# ControllerV3_0_1.net
KiCad netlist of a schematic drawn in Altium Designer
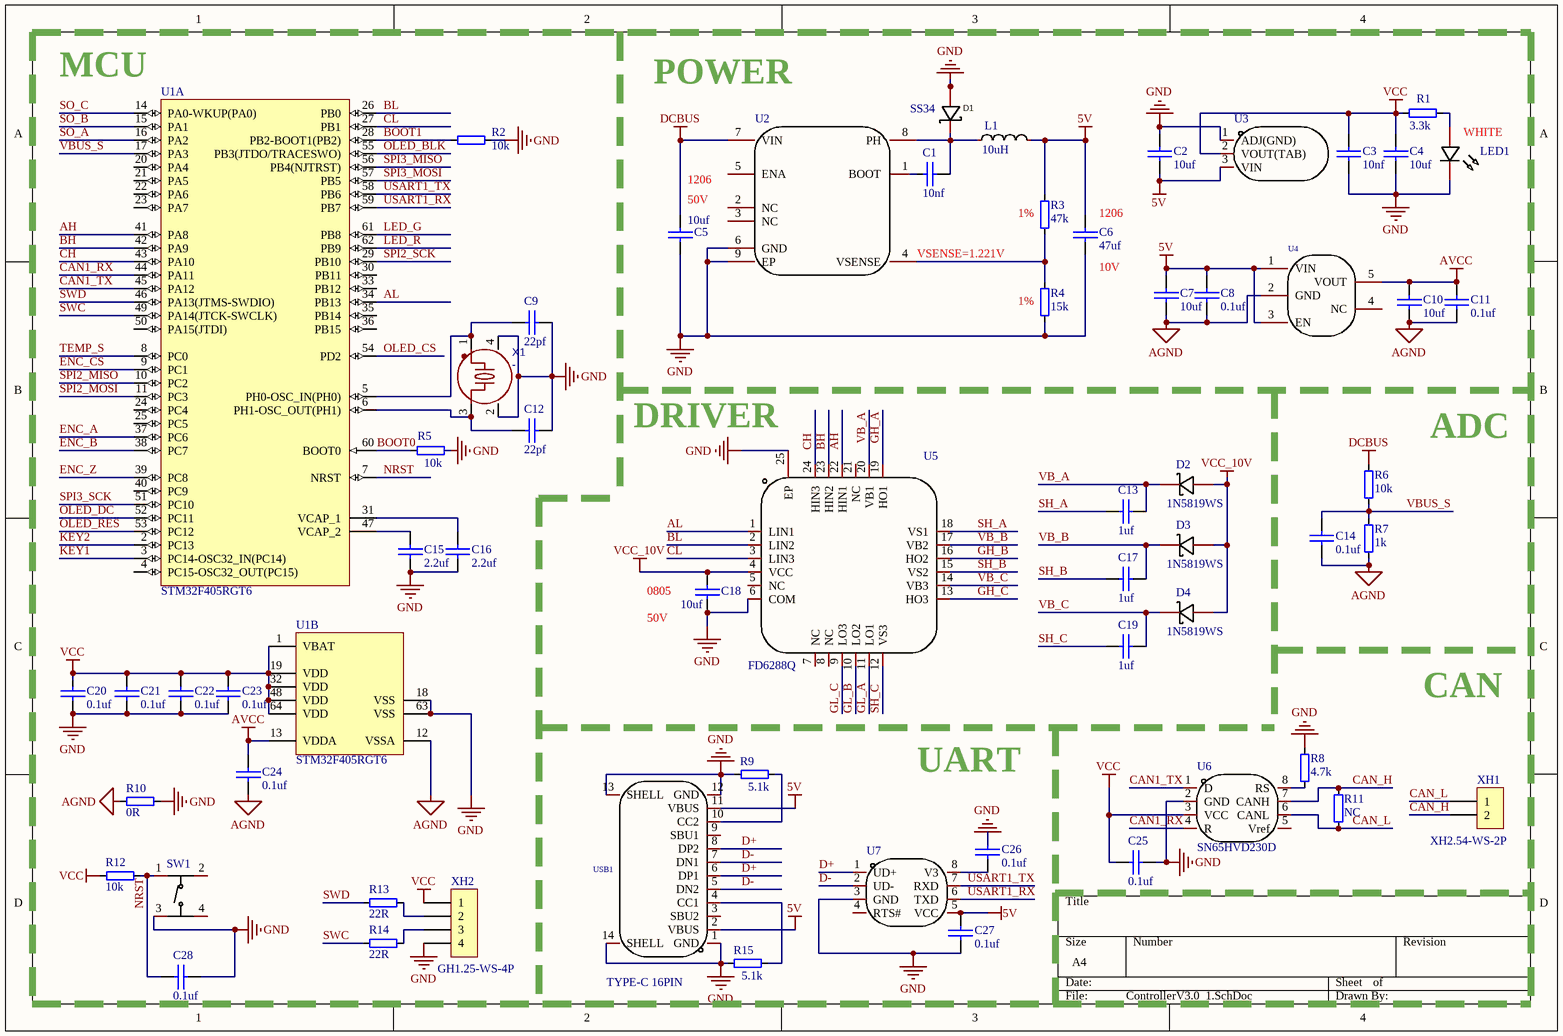
[diagram p0: ControllerV3.0_1.SchDoc]

(export (version "E")
  (design (tool "Eeschema 10.0.6"))
  (components
    (comp (ref "C1")
      (value "10nf")
      (footprint "0603C")
      (description "贴片电容")
      (libsource (lib "Controller") (part "CAP"))
    )
    (comp (ref "C2")
      (value "10uf")
      (footprint "0603C")
      (description "贴片电容")
      (libsource (lib "Controller") (part "CAP"))
    )
    (comp (ref "C3")
      (value "10nf")
      (footprint "0603C")
      (description "贴片电容")
      (libsource (lib "Controller") (part "CAP"))
    )
    (comp (ref "C4")
      (value "10uf")
      (footprint "0603C")
      (description "贴片电容")
      (libsource (lib "Controller") (part "CAP"))
    )
    (comp (ref "C5")
      (value "10uf")
      (footprint "1206C")
      (description "贴片电容")
      (libsource (lib "Controller") (part "CAP"))
    )
    (comp (ref "C6")
      (value "47uf")
      (footprint "1206C")
      (description "贴片电容")
      (libsource (lib "Controller") (part "CAP"))
    )
    (comp (ref "C7")
      (value "10uf")
      (footprint "0603C")
      (description "贴片电容")
      (libsource (lib "Controller") (part "CAP"))
    )
    (comp (ref "C8")
      (value "0.1uf")
      (footprint "0603C")
      (description "贴片电容")
      (libsource (lib "Controller") (part "CAP"))
    )
    (comp (ref "C9")
      (value "22pf")
      (footprint "0603C")
      (description "贴片电容")
      (libsource (lib "Controller") (part "CAP"))
    )
    (comp (ref "C10")
      (value "10uf")
      (footprint "0603C")
      (description "贴片电容")
      (libsource (lib "Controller") (part "CAP"))
    )
    (comp (ref "C11")
      (value "0.1uf")
      (footprint "0603C")
      (description "贴片电容")
      (libsource (lib "Controller") (part "CAP"))
    )
    (comp (ref "C12")
      (value "22pf")
      (footprint "0603C")
      (description "贴片电容")
      (libsource (lib "Controller") (part "CAP"))
    )
    (comp (ref "C13")
      (value "1uf")
      (footprint "0603C")
      (description "贴片电容")
      (libsource (lib "Controller") (part "CAP"))
    )
    (comp (ref "C14")
      (value "0.1uf")
      (footprint "0603C")
      (description "贴片电容")
      (libsource (lib "Controller") (part "CAP"))
    )
    (comp (ref "C15")
      (value "2.2uf")
      (footprint "0603C")
      (description "贴片电容")
      (libsource (lib "Controller") (part "CAP"))
    )
    (comp (ref "C16")
      (value "2.2uf")
      (footprint "0603C")
      (description "贴片电容")
      (libsource (lib "Controller") (part "CAP"))
    )
    (comp (ref "C17")
      (value "1uf")
      (footprint "0603C")
      (description "贴片电容")
      (libsource (lib "Controller") (part "CAP"))
    )
    (comp (ref "C18")
      (value "10uf")
      (footprint "0805C")
      (description "贴片电容")
      (libsource (lib "Controller") (part "CAP"))
    )
    (comp (ref "C19")
      (value "1uf")
      (footprint "0603C")
      (description "贴片电容")
      (libsource (lib "Controller") (part "CAP"))
    )
    (comp (ref "C20")
      (value "0.1uf")
      (footprint "0603C")
      (description "贴片电容")
      (libsource (lib "Controller") (part "CAP"))
    )
    (comp (ref "C21")
      (value "0.1uf")
      (footprint "0603C")
      (description "贴片电容")
      (libsource (lib "Controller") (part "CAP"))
    )
    (comp (ref "C22")
      (value "0.1uf")
      (footprint "0603C")
      (description "贴片电容")
      (libsource (lib "Controller") (part "CAP"))
    )
    (comp (ref "C23")
      (value "0.1uf")
      (footprint "0603C")
      (description "贴片电容")
      (libsource (lib "Controller") (part "CAP"))
    )
    (comp (ref "C24")
      (value "0.1uf")
      (footprint "0603C")
      (description "贴片电容")
      (libsource (lib "Controller") (part "CAP"))
    )
    (comp (ref "C25")
      (value "0.1uf")
      (footprint "0603C")
      (description "贴片电容")
      (libsource (lib "Controller") (part "CAP"))
    )
    (comp (ref "C26")
      (value "0.1uf")
      (footprint "0603C")
      (description "贴片电容")
      (libsource (lib "Controller") (part "CAP"))
    )
    (comp (ref "C27")
      (value "0.1uf")
      (footprint "0603C")
      (description "贴片电容")
      (libsource (lib "Controller") (part "CAP"))
    )
    (comp (ref "C28")
      (value "0.1uf")
      (footprint "0603C")
      (description "贴片电容")
      (libsource (lib "Controller") (part "CAP"))
    )
    (comp (ref "D1")
      (value "SS34")
      (footprint "SS34")
      (description "肖特基二极管")
      (fields (field (name "MANUFACTURER") "MDD"))
      (libsource (lib "Controller") (part "SS34"))
    )
    (comp (ref "D2")
      (value "1N5819WS")
      (footprint "SOD-323")
      (description "肖特基二极管")
      (fields (field (name "MANUFACTURER") "Hottech(合科泰)"))
      (libsource (lib "Controller") (part "1N5819WS"))
    )
    (comp (ref "D3")
      (value "1N5819WS")
      (footprint "SOD-323")
      (description "肖特基二极管")
      (fields (field (name "MANUFACTURER") "Hottech(合科泰)"))
      (libsource (lib "Controller") (part "1N5819WS"))
    )
    (comp (ref "D4")
      (value "1N5819WS")
      (footprint "SOD-323")
      (description "肖特基二极管")
      (fields (field (name "MANUFACTURER") "Hottech(合科泰)"))
      (libsource (lib "Controller") (part "1N5819WS"))
    )
    (comp (ref "L1")
      (value "10uH")
      (footprint "SMD-0420")
      (description "功率电感")
      (libsource (lib "Controller") (part "IND"))
    )
    (comp (ref "LED1")
      (value "LED_0603-B")
      (footprint "LED_0603")
      (libsource (lib "Controller") (part "LED"))
    )
    (comp (ref "R1")
      (value "3.3k")
      (footprint "0603R")
      (description "贴片电阻")
      (libsource (lib "Controller") (part "RES"))
    )
    (comp (ref "R2")
      (value "10k")
      (footprint "0603R")
      (description "贴片电阻")
      (libsource (lib "Controller") (part "RES"))
    )
    (comp (ref "R3")
      (value "47k")
      (footprint "0603R")
      (description "贴片电阻")
      (libsource (lib "Controller") (part "RES"))
    )
    (comp (ref "R4")
      (value "15k")
      (footprint "0603R")
      (description "贴片电阻")
      (libsource (lib "Controller") (part "RES"))
    )
    (comp (ref "R5")
      (value "10k")
      (footprint "0603R")
      (description "贴片电阻")
      (libsource (lib "Controller") (part "RES"))
    )
    (comp (ref "R6")
      (value "10k")
      (footprint "0603R")
      (description "贴片电阻")
      (libsource (lib "Controller") (part "RES"))
    )
    (comp (ref "R7")
      (value "1k")
      (footprint "0603R")
      (description "贴片电阻")
      (libsource (lib "Controller") (part "RES"))
    )
    (comp (ref "R8")
      (value "4.7k")
      (footprint "0603R")
      (description "贴片电阻")
      (libsource (lib "Controller") (part "RES"))
    )
    (comp (ref "R9")
      (value "5.1k")
      (footprint "0603R")
      (description "贴片电阻")
      (libsource (lib "Controller") (part "RES"))
    )
    (comp (ref "R10")
      (value "0R")
      (footprint "0603R")
      (description "贴片电阻")
      (libsource (lib "Controller") (part "RES"))
    )
    (comp (ref "R11")
      (value "NC")
      (footprint "0603R")
      (description "贴片电阻")
      (libsource (lib "Controller") (part "RES"))
    )
    (comp (ref "R12")
      (value "10k")
      (footprint "0603R")
      (description "贴片电阻")
      (libsource (lib "Controller") (part "RES"))
    )
    (comp (ref "R13")
      (value "22R")
      (footprint "0603R")
      (description "贴片电阻")
      (libsource (lib "Controller") (part "RES"))
    )
    (comp (ref "R14")
      (value "22R")
      (footprint "0603R")
      (description "贴片电阻")
      (libsource (lib "Controller") (part "RES"))
    )
    (comp (ref "R15")
      (value "5.1k")
      (footprint "0603R")
      (description "贴片电阻")
      (libsource (lib "Controller") (part "RES"))
    )
    (comp (ref "SW1")
      (value "TS-1187A-B-A-B")
      (footprint "TSW SMD-4*4*1.5")
      (description "轻触开关")
      (fields (field (name "MANUFACTURER") "XKB Connectivity(中国星坤)"))
      (libsource (lib "Controller") (part "TS-1187A-B-A-B"))
    )
    (comp (ref "U1")
      (value "STM32F405RGT6")
      (footprint "LQFP_64")
      (fields (field (name "MANUFACTURER") "STMicroelectronics"))
      (libsource (lib "Controller") (part "STM32F405RGT6"))
    )
    (comp (ref "U2")
      (value "TPS5450DDAR")
      (footprint "SOP-8-EP")
      (fields (field (name "MANUFACTURER") "TI(德州仪器)"))
      (libsource (lib "Controller") (part "TPS5450DDAR"))
    )
    (comp (ref "U3")
      (value "AMS1117-3.3_C347256")
      (footprint "SOT-89")
      (description "输出类型:固定;输出极性:正;最大输入电压:18V;输出电压:3.3V;输出电流:1A;电源纹波抑制比(PSRR):60dB@(120Hz);")
      (fields (field (name "MANUFACTURER") "UMW(友台半导体)") (field (name "MANUFACTURER PART") "AMS1117-3.3"))
      (libsource (lib "Controller") (part "AMS1117-3.3_C347256"))
    )
    (comp (ref "U4")
      (value "RT9013-33GB")
      (footprint "SOT-23-5")
      (description "输出类型:固定;输出极性:正;最大输入电压:5.5V;输出电压:3.3V;输出电流:500mA;电源纹波抑制比(PSRR):50dB@(10kHz);")
      (fields (field (name "MANUFACTURER") "RICHTEK(立锜)"))
      (libsource (lib "Controller") (part "RT9013-33GB"))
    )
    (comp (ref "U5")
      (value "FD6288Q")
      (footprint "QFN-24-EP(4x4)")
      (fields (field (name "MANUFACTURER") "Fortior Tech(峰岹)"))
      (libsource (lib "Controller") (part "FD6288Q"))
    )
    (comp (ref "U6")
      (value "SN65HVD230D")
      (footprint "SOP-8")
      (description "具有待机模式的 3.3V CAN 收发器 8-SOIC -40 to 85")
      (fields (field (name "MANUFACTURER") "TI(德州仪器)"))
      (libsource (lib "Controller") (part "SN65HVD230D"))
    )
    (comp (ref "U7")
      (value "CH340N")
      (footprint "SOP-8")
      (fields (field (name "MANUFACTURER") "WCH(南京沁恒)"))
      (libsource (lib "Controller") (part "CH340N"))
    )
    (comp (ref "USB1")
      (value "TYPE-C 16PIN")
      (footprint "USB-C-SMD_TYPE-C-6PIN-2MD-073")
      (description "连接器类型:Type-C;标准:-;公母:母座;触点数量:16;端口数量:1;安装方式:卧贴;额定电流 - 电源:5A;工作温度范围:-25℃~+85℃;")
      (fields
        (field (name "MANUFACTURER") "SHOU HAN(首韩)")
        (field (name "MANUFACTURER PART") "TYPE-C 16PIN 2MD(073)")
      )
      (libsource (lib "Controller") (part "TYPE-C 16PIN 2MD(073)"))
    )
    (comp (ref "X1")
      (value "-")
      (footprint "OSC 3225-4P")
      (description "8MHz")
      (fields
        (field (name "BOM_SUPPLIER PART") "C843260")
        (field (name "BOM_MANUFACTURER PART") "NX2016SA-32MHZ-STD-CZS-5")
        (field (name "CONTRIBUTOR") "LCSC")
      )
      (libsource (lib "Controller") (part "四脚无源晶振"))
    )
    (comp (ref "XH1")
      (value "XH2.54-WS-2P")
      (footprint "XH2.54-WS-2P")
      (libsource (lib "Controller") (part "XH2.54-WS-2P"))
    )
    (comp (ref "XH2")
      (value "GH1.25-WS-4P")
      (footprint "GH1.25-WS-4P")
      (libsource (lib "Controller") (part "GH1.25-WS-4P"))
    )
  )
  (nets
    (net (code "1") (name "/AH") (class "Default")
      (node (ref "U1") (pin "41") (pinfunction "PA8_41") (pintype "bidirectional"))
      (node (ref "U5") (pin "22") (pinfunction "HIN1_22") (pintype "passive"))
    )
    (net (code "2") (name "/AL") (class "Default")
      (node (ref "U1") (pin "34") (pinfunction "PB13_34") (pintype "bidirectional"))
      (node (ref "U5") (pin "1") (pinfunction "LIN1_1") (pintype "passive"))
    )
    (net (code "3") (name "/BH") (class "Default")
      (node (ref "U1") (pin "42") (pinfunction "PA9_42") (pintype "bidirectional"))
      (node (ref "U5") (pin "23") (pinfunction "HIN2_23") (pintype "passive"))
    )
    (net (code "4") (name "/BL") (class "Default")
      (node (ref "U1") (pin "26") (pinfunction "PB0_26") (pintype "bidirectional"))
      (node (ref "U5") (pin "2") (pinfunction "LIN2_2") (pintype "passive"))
    )
    (net (code "5") (name "/BOOT0") (class "Default")
      (node (ref "R5") (pin "1") (pinfunction "1_1") (pintype "passive"))
      (node (ref "U1") (pin "60") (pinfunction "BOOT0_60") (pintype "input"))
    )
    (net (code "6") (name "/BOOT1") (class "Default")
      (node (ref "R2") (pin "1") (pinfunction "1_1") (pintype "passive"))
      (node (ref "U1") (pin "28") (pinfunction "PB2-BOOT1(PB2)_28") (pintype "bidirectional"))
    )
    (net (code "7") (name "/CAN1_RX") (class "Default")
      (node (ref "U1") (pin "44") (pinfunction "PA11_44") (pintype "bidirectional"))
      (node (ref "U6") (pin "4") (pinfunction "R_4") (pintype "passive"))
    )
    (net (code "8") (name "/CAN1_TX") (class "Default")
      (node (ref "U1") (pin "45") (pinfunction "PA12_45") (pintype "bidirectional"))
      (node (ref "U6") (pin "1") (pinfunction "D_1") (pintype "passive"))
    )
    (net (code "9") (name "/CAN_H") (class "Default")
      (node (ref "R11") (pin "2") (pinfunction "2_2") (pintype "passive"))
      (node (ref "U6") (pin "7") (pinfunction "CANH_7") (pintype "passive"))
      (node (ref "XH1") (pin "2") (pinfunction "2_2") (pintype "passive"))
    )
    (net (code "10") (name "/CAN_L") (class "Default")
      (node (ref "R11") (pin "1") (pinfunction "1_1") (pintype "passive"))
      (node (ref "U6") (pin "6") (pinfunction "CANL_6") (pintype "passive"))
      (node (ref "XH1") (pin "1") (pinfunction "1_1") (pintype "passive"))
    )
    (net (code "11") (name "/CH") (class "Default")
      (node (ref "U1") (pin "43") (pinfunction "PA10_43") (pintype "bidirectional"))
      (node (ref "U5") (pin "24") (pinfunction "HIN3_24") (pintype "passive"))
    )
    (net (code "12") (name "/CL") (class "Default")
      (node (ref "U1") (pin "27") (pinfunction "PB1_27") (pintype "bidirectional"))
      (node (ref "U5") (pin "3") (pinfunction "LIN3_3") (pintype "passive"))
    )
    (net (code "13") (name "/D+") (class "Default")
      (node (ref "U7") (pin "1") (pinfunction "UD+_1") (pintype "passive"))
      (node (ref "USB1") (pin "6") (pinfunction "DP1_6") (pintype "passive"))
      (node (ref "USB1") (pin "8") (pinfunction "DP2_8") (pintype "passive"))
    )
    (net (code "14") (name "/D-") (class "Default")
      (node (ref "U7") (pin "2") (pinfunction "UD-_2") (pintype "passive"))
      (node (ref "USB1") (pin "5") (pinfunction "DN2_5") (pintype "passive"))
      (node (ref "USB1") (pin "7") (pinfunction "DN1_7") (pintype "passive"))
    )
    (net (code "15") (name "/ENC_A") (class "Default")
      (node (ref "U1") (pin "37") (pinfunction "PC6_37") (pintype "bidirectional"))
    )
    (net (code "16") (name "/ENC_B") (class "Default")
      (node (ref "U1") (pin "38") (pinfunction "PC7_38") (pintype "bidirectional"))
    )
    (net (code "17") (name "/ENC_CS") (class "Default")
      (node (ref "U1") (pin "9") (pinfunction "PC1_9") (pintype "bidirectional"))
    )
    (net (code "18") (name "/ENC_Z") (class "Default")
      (node (ref "U1") (pin "39") (pinfunction "PC8_39") (pintype "bidirectional"))
    )
    (net (code "19") (name "/GH_A") (class "Default")
      (node (ref "U5") (pin "19") (pinfunction "HO1_19") (pintype "passive"))
    )
    (net (code "20") (name "/GH_B") (class "Default")
      (node (ref "U5") (pin "16") (pinfunction "HO2_16") (pintype "passive"))
    )
    (net (code "21") (name "/GH_C") (class "Default")
      (node (ref "U5") (pin "13") (pinfunction "HO3_13") (pintype "passive"))
    )
    (net (code "22") (name "/GL_A") (class "Default")
      (node (ref "U5") (pin "11") (pinfunction "LO1_11") (pintype "passive"))
    )
    (net (code "23") (name "/GL_B") (class "Default")
      (node (ref "U5") (pin "10") (pinfunction "LO2_10") (pintype "passive"))
    )
    (net (code "24") (name "/GL_C") (class "Default")
      (node (ref "U5") (pin "9") (pinfunction "LO3_9") (pintype "passive"))
    )
    (net (code "25") (name "/KEY1") (class "Default")
      (node (ref "U1") (pin "3") (pinfunction "PC14-OSC32_IN(PC14)_3") (pintype "bidirectional"))
    )
    (net (code "26") (name "/KEY2") (class "Default")
      (node (ref "U1") (pin "2") (pinfunction "PC13_2") (pintype "bidirectional"))
    )
    (net (code "27") (name "/LED_G") (class "Default")
      (node (ref "U1") (pin "61") (pinfunction "PB8_61") (pintype "bidirectional"))
    )
    (net (code "28") (name "/LED_R") (class "Default")
      (node (ref "U1") (pin "62") (pinfunction "PB9_62") (pintype "bidirectional"))
    )
    (net (code "29") (name "/NRST") (class "Default")
      (node (ref "C28") (pin "1") (pinfunction "1_1") (pintype "passive"))
      (node (ref "R12") (pin "1") (pinfunction "1_1") (pintype "passive"))
      (node (ref "SW1") (pin "1") (pinfunction "A_1") (pintype "passive"))
      (node (ref "U1") (pin "7") (pinfunction "NRST_7") (pintype "bidirectional"))
    )
    (net (code "30") (name "/OLED_BLK") (class "Default")
      (node (ref "U1") (pin "55") (pinfunction "PB3(JTDO/TRACESWO)_55") (pintype "bidirectional"))
    )
    (net (code "31") (name "/OLED_CS") (class "Default")
      (node (ref "U1") (pin "54") (pinfunction "PD2_54") (pintype "bidirectional"))
    )
    (net (code "32") (name "/OLED_DC") (class "Default")
      (node (ref "U1") (pin "52") (pinfunction "PC11_52") (pintype "bidirectional"))
    )
    (net (code "33") (name "/OLED_RES") (class "Default")
      (node (ref "U1") (pin "53") (pinfunction "PC12_53") (pintype "bidirectional"))
    )
    (net (code "34") (name "/SH_A") (class "Default")
      (node (ref "C13") (pin "1") (pinfunction "1_1") (pintype "passive"))
      (node (ref "U5") (pin "18") (pinfunction "VS1_18") (pintype "passive"))
    )
    (net (code "35") (name "/SH_B") (class "Default")
      (node (ref "C17") (pin "1") (pinfunction "1_1") (pintype "passive"))
      (node (ref "U5") (pin "15") (pinfunction "VS2_15") (pintype "passive"))
    )
    (net (code "36") (name "/SH_C") (class "Default")
      (node (ref "C19") (pin "1") (pinfunction "1_1") (pintype "passive"))
      (node (ref "U5") (pin "12") (pinfunction "VS3_12") (pintype "passive"))
    )
    (net (code "37") (name "/SO_A") (class "Default")
      (node (ref "U1") (pin "16") (pinfunction "PA2_16") (pintype "bidirectional"))
    )
    (net (code "38") (name "/SO_B") (class "Default")
      (node (ref "U1") (pin "15") (pinfunction "PA1_15") (pintype "bidirectional"))
    )
    (net (code "39") (name "/SO_C") (class "Default")
      (node (ref "U1") (pin "14") (pinfunction "PA0-WKUP(PA0)_14") (pintype "bidirectional"))
    )
    (net (code "40") (name "/SPI2_MISO") (class "Default")
      (node (ref "U1") (pin "10") (pinfunction "PC2_10") (pintype "bidirectional"))
    )
    (net (code "41") (name "/SPI2_MOSI") (class "Default")
      (node (ref "U1") (pin "11") (pinfunction "PC3_11") (pintype "bidirectional"))
    )
    (net (code "42") (name "/SPI2_SCK") (class "Default")
      (node (ref "U1") (pin "29") (pinfunction "PB10_29") (pintype "bidirectional"))
    )
    (net (code "43") (name "/SPI3_MISO") (class "Default")
      (node (ref "U1") (pin "56") (pinfunction "PB4(NJTRST)_56") (pintype "bidirectional"))
    )
    (net (code "44") (name "/SPI3_MOSI") (class "Default")
      (node (ref "U1") (pin "57") (pinfunction "PB5_57") (pintype "bidirectional"))
    )
    (net (code "45") (name "/SPI3_SCK") (class "Default")
      (node (ref "U1") (pin "51") (pinfunction "PC10_51") (pintype "bidirectional"))
    )
    (net (code "46") (name "/SWC") (class "Default")
      (node (ref "R14") (pin "1") (pinfunction "1_1") (pintype "passive"))
      (node (ref "U1") (pin "49") (pinfunction "PA14(JTCK-SWCLK)_49") (pintype "bidirectional"))
    )
    (net (code "47") (name "/SWD") (class "Default")
      (node (ref "R13") (pin "1") (pinfunction "1_1") (pintype "passive"))
      (node (ref "U1") (pin "46") (pinfunction "PA13(JTMS-SWDIO)_46") (pintype "bidirectional"))
    )
    (net (code "48") (name "/TEMP_S") (class "Default")
      (node (ref "U1") (pin "8") (pinfunction "PC0_8") (pintype "bidirectional"))
    )
    (net (code "49") (name "/USART1_RX") (class "Default")
      (node (ref "U1") (pin "59") (pinfunction "PB7_59") (pintype "bidirectional"))
      (node (ref "U7") (pin "6") (pinfunction "TXD_6") (pintype "passive"))
    )
    (net (code "50") (name "/USART1_TX") (class "Default")
      (node (ref "U1") (pin "58") (pinfunction "PB6_58") (pintype "bidirectional"))
      (node (ref "U7") (pin "7") (pinfunction "RXD_7") (pintype "passive"))
    )
    (net (code "51") (name "/VBUS_S") (class "Default")
      (node (ref "C14") (pin "1") (pinfunction "1_1") (pintype "passive"))
      (node (ref "R6") (pin "1") (pinfunction "1_1") (pintype "passive"))
      (node (ref "R7") (pin "2") (pinfunction "2_2") (pintype "passive"))
      (node (ref "U1") (pin "17") (pinfunction "PA3_17") (pintype "bidirectional"))
    )
    (net (code "52") (name "/VB_A") (class "Default")
      (node (ref "C13") (pin "2") (pinfunction "2_2") (pintype "passive"))
      (node (ref "D2") (pin "1") (pinfunction "K_1") (pintype "passive"))
      (node (ref "U5") (pin "20") (pinfunction "VB1_20") (pintype "passive"))
    )
    (net (code "53") (name "/VB_B") (class "Default")
      (node (ref "C17") (pin "2") (pinfunction "2_2") (pintype "passive"))
      (node (ref "D3") (pin "1") (pinfunction "K_1") (pintype "passive"))
      (node (ref "U5") (pin "17") (pinfunction "VB2_17") (pintype "passive"))
    )
    (net (code "54") (name "/VB_C") (class "Default")
      (node (ref "C19") (pin "2") (pinfunction "2_2") (pintype "passive"))
      (node (ref "D4") (pin "1") (pinfunction "K_1") (pintype "passive"))
      (node (ref "U5") (pin "14") (pinfunction "VB3_14") (pintype "passive"))
    )
    (net (code "55") (name "5V") (class "Default")
      (node (ref "C2") (pin "2") (pinfunction "2_2") (pintype "passive"))
      (node (ref "C27") (pin "1") (pinfunction "1_1") (pintype "passive"))
      (node (ref "C6") (pin "1") (pinfunction "1_1") (pintype "passive"))
      (node (ref "C7") (pin "1") (pinfunction "1_1") (pintype "passive"))
      (node (ref "C8") (pin "1") (pinfunction "1_1") (pintype "passive"))
      (node (ref "L1") (pin "2") (pinfunction "2_2") (pintype "passive"))
      (node (ref "R3") (pin "2") (pinfunction "2_2") (pintype "passive"))
      (node (ref "U3") (pin "3") (pinfunction "VIN_3") (pintype "passive"))
      (node (ref "U4") (pin "1") (pinfunction "VIN_1") (pintype "passive"))
      (node (ref "U4") (pin "3") (pinfunction "EN_3") (pintype "passive"))
      (node (ref "U7") (pin "5") (pinfunction "VCC_5") (pintype "passive"))
      (node (ref "USB1") (pin "11") (pinfunction "VBUS_11") (pintype "passive"))
      (node (ref "USB1") (pin "2") (pinfunction "VBUS_2") (pintype "passive"))
    )
    (net (code "56") (name "AGND") (class "Default")
      (node (ref "C10") (pin "2") (pinfunction "2_2") (pintype "passive"))
      (node (ref "C11") (pin "2") (pinfunction "2_2") (pintype "passive"))
      (node (ref "C14") (pin "2") (pinfunction "2_2") (pintype "passive"))
      (node (ref "C24") (pin "2") (pinfunction "2_2") (pintype "passive"))
      (node (ref "C7") (pin "2") (pinfunction "2_2") (pintype "passive"))
      (node (ref "C8") (pin "2") (pinfunction "2_2") (pintype "passive"))
      (node (ref "R10") (pin "2") (pinfunction "2_2") (pintype "passive"))
      (node (ref "R7") (pin "1") (pinfunction "1_1") (pintype "passive"))
      (node (ref "U1") (pin "12") (pinfunction "VSSA_12") (pintype "power_in"))
      (node (ref "U4") (pin "2") (pinfunction "GND_2") (pintype "passive"))
    )
    (net (code "57") (name "AVCC") (class "Default")
      (node (ref "C10") (pin "1") (pinfunction "1_1") (pintype "passive"))
      (node (ref "C11") (pin "1") (pinfunction "1_1") (pintype "passive"))
      (node (ref "C24") (pin "1") (pinfunction "1_1") (pintype "passive"))
      (node (ref "U1") (pin "13") (pinfunction "VDDA_13") (pintype "power_in"))
      (node (ref "U4") (pin "5") (pinfunction "VOUT_5") (pintype "passive"))
    )
    (net (code "58") (name "DCBUS") (class "Default")
      (node (ref "C5") (pin "1") (pinfunction "1_1") (pintype "passive"))
      (node (ref "R6") (pin "2") (pinfunction "2_2") (pintype "passive"))
      (node (ref "U2") (pin "7") (pinfunction "VIN_7") (pintype "passive"))
    )
    (net (code "59") (name "GND") (class "Default")
      (node (ref "C12") (pin "2") (pinfunction "2_2") (pintype "passive"))
      (node (ref "C15") (pin "2") (pinfunction "2_2") (pintype "passive"))
      (node (ref "C16") (pin "2") (pinfunction "2_2") (pintype "passive"))
      (node (ref "C18") (pin "2") (pinfunction "2_2") (pintype "passive"))
      (node (ref "C2") (pin "1") (pinfunction "1_1") (pintype "passive"))
      (node (ref "C20") (pin "2") (pinfunction "2_2") (pintype "passive"))
      (node (ref "C21") (pin "2") (pinfunction "2_2") (pintype "passive"))
      (node (ref "C22") (pin "2") (pinfunction "2_2") (pintype "passive"))
      (node (ref "C23") (pin "2") (pinfunction "2_2") (pintype "passive"))
      (node (ref "C25") (pin "2") (pinfunction "2_2") (pintype "passive"))
      (node (ref "C26") (pin "2") (pinfunction "2_2") (pintype "passive"))
      (node (ref "C27") (pin "2") (pinfunction "2_2") (pintype "passive"))
      (node (ref "C28") (pin "2") (pinfunction "2_2") (pintype "passive"))
      (node (ref "C3") (pin "2") (pinfunction "2_2") (pintype "passive"))
      (node (ref "C4") (pin "2") (pinfunction "2_2") (pintype "passive"))
      (node (ref "C5") (pin "2") (pinfunction "2_2") (pintype "passive"))
      (node (ref "C6") (pin "2") (pinfunction "2_2") (pintype "passive"))
      (node (ref "C9") (pin "2") (pinfunction "2_2") (pintype "passive"))
      (node (ref "D1") (pin "2") (pinfunction "A_2") (pintype "passive"))
      (node (ref "LED1") (pin "1") (pinfunction "C_1") (pintype "passive"))
      (node (ref "R10") (pin "1") (pinfunction "1_1") (pintype "passive"))
      (node (ref "R15") (pin "1") (pinfunction "1_1") (pintype "passive"))
      (node (ref "R2") (pin "2") (pinfunction "2_2") (pintype "passive"))
      (node (ref "R4") (pin "1") (pinfunction "1_1") (pintype "passive"))
      (node (ref "R5") (pin "2") (pinfunction "2_2") (pintype "passive"))
      (node (ref "R8") (pin "2") (pinfunction "2_2") (pintype "passive"))
      (node (ref "R9") (pin "1") (pinfunction "1_1") (pintype "passive"))
      (node (ref "SW1") (pin "3") (pinfunction "C_3") (pintype "passive"))
      (node (ref "U1") (pin "18") (pinfunction "VSS_18") (pintype "power_in"))
      (node (ref "U1") (pin "63") (pinfunction "VSS_63") (pintype "power_in"))
      (node (ref "U2") (pin "6") (pinfunction "GND_6") (pintype "passive"))
      (node (ref "U2") (pin "9") (pinfunction "EP_9") (pintype "passive"))
      (node (ref "U3") (pin "1") (pinfunction "ADJ(GND)_1") (pintype "passive"))
      (node (ref "U5") (pin "25") (pinfunction "EP_25") (pintype "passive"))
      (node (ref "U5") (pin "6") (pinfunction "COM_6") (pintype "passive"))
      (node (ref "U6") (pin "2") (pinfunction "GND_2") (pintype "passive"))
      (node (ref "U7") (pin "3") (pinfunction "GND_3") (pintype "passive"))
      (node (ref "USB1") (pin "1") (pinfunction "GND_1") (pintype "passive"))
      (node (ref "USB1") (pin "12") (pinfunction "GND_12") (pintype "passive"))
      (node (ref "USB1") (pin "13") (pinfunction "SHELL_13") (pintype "passive"))
      (node (ref "USB1") (pin "14") (pinfunction "SHELL_14") (pintype "passive"))
      (node (ref "X1") (pin "2") (pinfunction "GND_2") (pintype "passive"))
      (node (ref "X1") (pin "4") (pinfunction "GND_4") (pintype "passive"))
      (node (ref "XH2") (pin "4") (pinfunction "4_4") (pintype "passive"))
    )
    (net (code "60") (name "Net-(D1-K)") (class "Default")
      (node (ref "C1") (pin "2") (pinfunction "2_2") (pintype "passive"))
      (node (ref "D1") (pin "1") (pinfunction "K_1") (pintype "passive"))
      (node (ref "L1") (pin "1") (pinfunction "1_1") (pintype "passive"))
      (node (ref "U2") (pin "8") (pinfunction "PH_8") (pintype "passive"))
    )
    (net (code "61") (name "Net-(LED1-A)") (class "Default")
      (node (ref "LED1") (pin "2") (pinfunction "A_2") (pintype "passive"))
      (node (ref "R1") (pin "1") (pinfunction "1_1") (pintype "passive"))
    )
    (net (code "62") (name "Net-(R13-Pad2)") (class "Default")
      (node (ref "R13") (pin "2") (pinfunction "2_2") (pintype "passive"))
      (node (ref "XH2") (pin "2") (pinfunction "2_2") (pintype "passive"))
    )
    (net (code "63") (name "Net-(R14-Pad2)") (class "Default")
      (node (ref "R14") (pin "2") (pinfunction "2_2") (pintype "passive"))
      (node (ref "XH2") (pin "3") (pinfunction "3_3") (pintype "passive"))
    )
    (net (code "64") (name "Net-(U1A-PH0-OSC_IN(PH0))") (class "Default")
      (node (ref "C9") (pin "1") (pinfunction "1_1") (pintype "passive"))
      (node (ref "U1") (pin "5") (pinfunction "PH0-OSC_IN(PH0)_5") (pintype "bidirectional"))
      (node (ref "X1") (pin "1") (pinfunction "1_1") (pintype "passive"))
    )
    (net (code "65") (name "Net-(U1A-PH1-OSC_OUT(PH1))") (class "Default")
      (node (ref "C12") (pin "1") (pinfunction "1_1") (pintype "passive"))
      (node (ref "U1") (pin "6") (pinfunction "PH1-OSC_OUT(PH1)_6") (pintype "bidirectional"))
      (node (ref "X1") (pin "3") (pinfunction "3_3") (pintype "passive"))
    )
    (net (code "66") (name "Net-(U1A-VCAP_1)") (class "Default")
      (node (ref "C16") (pin "1") (pinfunction "1_1") (pintype "passive"))
      (node (ref "U1") (pin "31") (pinfunction "VCAP_1_31") (pintype "power_in"))
    )
    (net (code "67") (name "Net-(U1A-VCAP_2)") (class "Default")
      (node (ref "C15") (pin "1") (pinfunction "1_1") (pintype "passive"))
      (node (ref "U1") (pin "47") (pinfunction "VCAP_2_47") (pintype "power_in"))
    )
    (net (code "68") (name "Net-(U2-BOOT)") (class "Default")
      (node (ref "C1") (pin "1") (pinfunction "1_1") (pintype "passive"))
      (node (ref "U2") (pin "1") (pinfunction "BOOT_1") (pintype "passive"))
    )
    (net (code "69") (name "Net-(U2-VSENSE)") (class "Default")
      (node (ref "R3") (pin "1") (pinfunction "1_1") (pintype "passive"))
      (node (ref "R4") (pin "2") (pinfunction "2_2") (pintype "passive"))
      (node (ref "U2") (pin "4") (pinfunction "VSENSE_4") (pintype "passive"))
    )
    (net (code "70") (name "Net-(U6-RS)") (class "Default")
      (node (ref "R8") (pin "1") (pinfunction "1_1") (pintype "passive"))
      (node (ref "U6") (pin "8") (pinfunction "RS_8") (pintype "passive"))
    )
    (net (code "71") (name "Net-(U7-V3)") (class "Default")
      (node (ref "C26") (pin "1") (pinfunction "1_1") (pintype "passive"))
      (node (ref "U7") (pin "8") (pinfunction "V3_8") (pintype "passive"))
    )
    (net (code "72") (name "Net-(USB1-CC1)") (class "Default")
      (node (ref "R15") (pin "2") (pinfunction "2_2") (pintype "passive"))
      (node (ref "USB1") (pin "4") (pinfunction "CC1_4") (pintype "passive"))
    )
    (net (code "73") (name "Net-(USB1-CC2)") (class "Default")
      (node (ref "R9") (pin "2") (pinfunction "2_2") (pintype "passive"))
      (node (ref "USB1") (pin "10") (pinfunction "CC2_10") (pintype "passive"))
    )
    (net (code "74") (name "VCC") (class "Default")
      (node (ref "C20") (pin "1") (pinfunction "1_1") (pintype "passive"))
      (node (ref "C21") (pin "1") (pinfunction "1_1") (pintype "passive"))
      (node (ref "C22") (pin "1") (pinfunction "1_1") (pintype "passive"))
      (node (ref "C23") (pin "1") (pinfunction "1_1") (pintype "passive"))
      (node (ref "C25") (pin "1") (pinfunction "1_1") (pintype "passive"))
      (node (ref "C3") (pin "1") (pinfunction "1_1") (pintype "passive"))
      (node (ref "C4") (pin "1") (pinfunction "1_1") (pintype "passive"))
      (node (ref "R1") (pin "2") (pinfunction "2_2") (pintype "passive"))
      (node (ref "R12") (pin "2") (pinfunction "2_2") (pintype "passive"))
      (node (ref "U1") (pin "1") (pinfunction "VBAT_1") (pintype "power_in"))
      (node (ref "U1") (pin "19") (pinfunction "VDD_19") (pintype "power_in"))
      (node (ref "U1") (pin "32") (pinfunction "VDD_32") (pintype "power_in"))
      (node (ref "U1") (pin "48") (pinfunction "VDD_48") (pintype "power_in"))
      (node (ref "U1") (pin "64") (pinfunction "VDD_64") (pintype "power_in"))
      (node (ref "U3") (pin "2") (pinfunction "VOUT(TAB)_2") (pintype "passive"))
      (node (ref "U6") (pin "3") (pinfunction "VCC_3") (pintype "passive"))
      (node (ref "XH2") (pin "1") (pinfunction "1_1") (pintype "passive"))
    )
    (net (code "75") (name "VCC_10V") (class "Default")
      (node (ref "C18") (pin "1") (pinfunction "1_1") (pintype "passive"))
      (node (ref "D2") (pin "2") (pinfunction "A_2") (pintype "passive"))
      (node (ref "D3") (pin "2") (pinfunction "A_2") (pintype "passive"))
      (node (ref "D4") (pin "2") (pinfunction "A_2") (pintype "passive"))
      (node (ref "U5") (pin "4") (pinfunction "VCC_4") (pintype "passive"))
    )
    (net (code "76") (name "unconnected-(SW1-B-Pad2)") (class "Default")
      (node (ref "SW1") (pin "2") (pinfunction "B_2") (pintype "passive"))
    )
    (net (code "77") (name "unconnected-(SW1-D-Pad4)") (class "Default")
      (node (ref "SW1") (pin "4") (pinfunction "D_4") (pintype "passive"))
    )
    (net (code "78") (name "unconnected-(U1A-PA4-Pad20)") (class "Default")
      (node (ref "U1") (pin "20") (pinfunction "PA4_20") (pintype "bidirectional"))
    )
    (net (code "79") (name "unconnected-(U1A-PA5-Pad21)") (class "Default")
      (node (ref "U1") (pin "21") (pinfunction "PA5_21") (pintype "bidirectional"))
    )
    (net (code "80") (name "unconnected-(U1A-PA6-Pad22)") (class "Default")
      (node (ref "U1") (pin "22") (pinfunction "PA6_22") (pintype "bidirectional"))
    )
    (net (code "81") (name "unconnected-(U1A-PA7-Pad23)") (class "Default")
      (node (ref "U1") (pin "23") (pinfunction "PA7_23") (pintype "bidirectional"))
    )
    (net (code "82") (name "unconnected-(U1A-PA15(JTDI)-Pad50)") (class "Default")
      (node (ref "U1") (pin "50") (pinfunction "PA15(JTDI)_50") (pintype "bidirectional"))
    )
    (net (code "83") (name "unconnected-(U1A-PB11-Pad30)") (class "Default")
      (node (ref "U1") (pin "30") (pinfunction "PB11_30") (pintype "bidirectional"))
    )
    (net (code "84") (name "unconnected-(U1A-PB12-Pad33)") (class "Default")
      (node (ref "U1") (pin "33") (pinfunction "PB12_33") (pintype "bidirectional"))
    )
    (net (code "85") (name "unconnected-(U1A-PB14-Pad35)") (class "Default")
      (node (ref "U1") (pin "35") (pinfunction "PB14_35") (pintype "bidirectional"))
    )
    (net (code "86") (name "unconnected-(U1A-PB15-Pad36)") (class "Default")
      (node (ref "U1") (pin "36") (pinfunction "PB15_36") (pintype "bidirectional"))
    )
    (net (code "87") (name "unconnected-(U1A-PC4-Pad24)") (class "Default")
      (node (ref "U1") (pin "24") (pinfunction "PC4_24") (pintype "bidirectional"))
    )
    (net (code "88") (name "unconnected-(U1A-PC5-Pad25)") (class "Default")
      (node (ref "U1") (pin "25") (pinfunction "PC5_25") (pintype "bidirectional"))
    )
    (net (code "89") (name "unconnected-(U1A-PC9-Pad40)") (class "Default")
      (node (ref "U1") (pin "40") (pinfunction "PC9_40") (pintype "bidirectional"))
    )
    (net (code "90") (name "unconnected-(U1A-PC15-OSC32_OUT(PC15)-Pad4)") (class "Default")
      (node (ref "U1") (pin "4") (pinfunction "PC15-OSC32_OUT(PC15)_4") (pintype "bidirectional"))
    )
    (net (code "91") (name "unconnected-(U2-ENA-Pad5)") (class "Default")
      (node (ref "U2") (pin "5") (pinfunction "ENA_5") (pintype "passive"))
    )
    (net (code "92") (name "unconnected-(U2-NC-Pad2)") (class "Default")
      (node (ref "U2") (pin "2") (pinfunction "NC_2") (pintype "passive"))
    )
    (net (code "93") (name "unconnected-(U2-NC-Pad3)") (class "Default")
      (node (ref "U2") (pin "3") (pinfunction "NC_3") (pintype "passive"))
    )
    (net (code "94") (name "unconnected-(U4-NC-Pad4)") (class "Default")
      (node (ref "U4") (pin "4") (pinfunction "NC_4") (pintype "passive"))
    )
    (net (code "95") (name "unconnected-(U5-NC-Pad5)") (class "Default")
      (node (ref "U5") (pin "5") (pinfunction "NC_5") (pintype "passive"))
    )
    (net (code "96") (name "unconnected-(U5-NC-Pad7)") (class "Default")
      (node (ref "U5") (pin "7") (pinfunction "NC_7") (pintype "passive"))
    )
    (net (code "97") (name "unconnected-(U5-NC-Pad8)") (class "Default")
      (node (ref "U5") (pin "8") (pinfunction "NC_8") (pintype "passive"))
    )
    (net (code "98") (name "unconnected-(U5-NC-Pad21)") (class "Default")
      (node (ref "U5") (pin "21") (pinfunction "NC_21") (pintype "passive"))
    )
    (net (code "99") (name "unconnected-(U6-Vref-Pad5)") (class "Default")
      (node (ref "U6") (pin "5") (pinfunction "Vref_5") (pintype "passive"))
    )
    (net (code "100") (name "unconnected-(U7-RTS#-Pad4)") (class "Default")
      (node (ref "U7") (pin "4") (pinfunction "RTS#_4") (pintype "passive"))
    )
    (net (code "101") (name "unconnected-(USB1-SBU1-Pad9)") (class "Default")
      (node (ref "USB1") (pin "9") (pinfunction "SBU1_9") (pintype "passive"))
    )
    (net (code "102") (name "unconnected-(USB1-SBU2-Pad3)") (class "Default")
      (node (ref "USB1") (pin "3") (pinfunction "SBU2_3") (pintype "passive"))
    )
  )
)
